# HomeSenseBasic.net
KiCad netlist of a schematic drawn in EAGLE
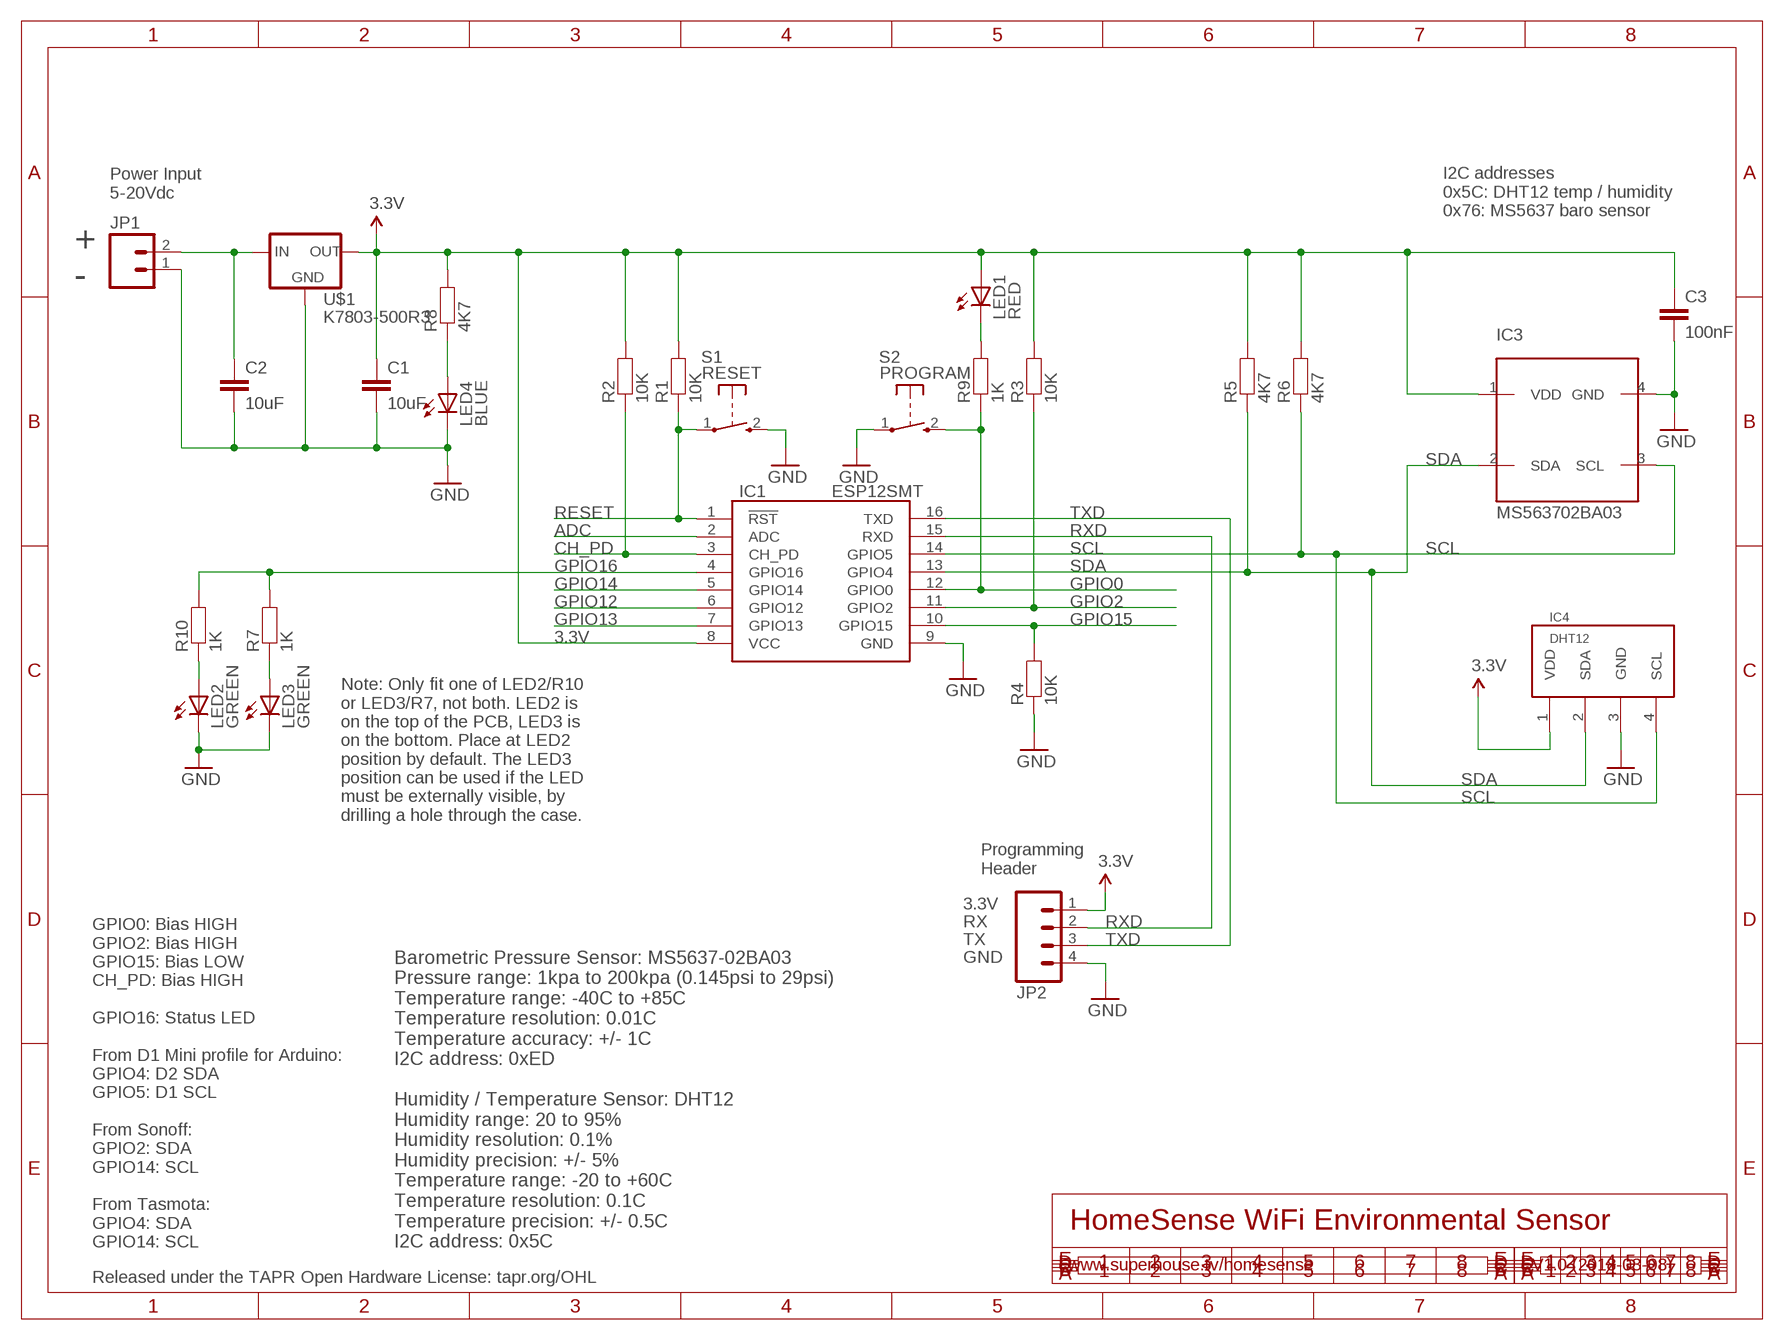
[diagram p0: schematic, sheet 1]

(export (version "E")
  (design (tool "Eeschema 10.0.6"))
  (components
    (comp (ref "C1")
      (value "10uF")
      (footprint "eagle-import:0805")
      (libsource (lib "eagle-import") (part "CAP0805"))
    )
    (comp (ref "C2")
      (value "10uF")
      (footprint "eagle-import:0805")
      (libsource (lib "eagle-import") (part "CAP0805"))
    )
    (comp (ref "C3")
      (value "100nF")
      (footprint "eagle-import:0603")
      (libsource (lib "eagle-import") (part "CAP0603"))
    )
    (comp (ref "IC1")
      (value "ESP12SMT")
      (footprint "eagle-import:ESP12")
      (libsource (lib "eagle-import") (part "ESP12SMT"))
    )
    (comp (ref "IC3")
      (value "MS563702BA03")
      (footprint "eagle-import:MS5637")
      (libsource (lib "eagle-import") (part "MS563702BA03"))
    )
    (comp (ref "IC4")
      (value "DHT12")
      (footprint "eagle-import:DHT12")
      (libsource (lib "eagle-import") (part "DHT12FLAT"))
    )
    (comp (ref "JP1")
      (value "M02PTH")
      (footprint "eagle-import:1X02")
      (libsource (lib "eagle-import") (part "M02PTH"))
    )
    (comp (ref "JP2")
      (value "M04PTH")
      (footprint "eagle-import:1X04")
      (libsource (lib "eagle-import") (part "M04PTH"))
    )
    (comp (ref "LED1")
      (value "RED")
      (footprint "eagle-import:LED-0603")
      (libsource (lib "eagle-import") (part "LED0603"))
    )
    (comp (ref "LED2")
      (value "GREEN")
      (footprint "eagle-import:LED-0603")
      (libsource (lib "eagle-import") (part "LED0603"))
    )
    (comp (ref "LED3")
      (value "GREEN")
      (footprint "eagle-import:LED-0603")
      (libsource (lib "eagle-import") (part "LED0603"))
    )
    (comp (ref "LED4")
      (value "BLUE")
      (footprint "eagle-import:LED-0603")
      (libsource (lib "eagle-import") (part "LED0603"))
    )
    (comp (ref "R1")
      (value "10K")
      (footprint "eagle-import:0603")
      (libsource (lib "eagle-import") (part "RESISTOR0603"))
    )
    (comp (ref "R2")
      (value "10K")
      (footprint "eagle-import:0603")
      (libsource (lib "eagle-import") (part "RESISTOR0603"))
    )
    (comp (ref "R3")
      (value "10K")
      (footprint "eagle-import:0603")
      (libsource (lib "eagle-import") (part "RESISTOR0603"))
    )
    (comp (ref "R4")
      (value "10K")
      (footprint "eagle-import:0603")
      (libsource (lib "eagle-import") (part "RESISTOR0603"))
    )
    (comp (ref "R5")
      (value "4K7")
      (footprint "eagle-import:0603")
      (libsource (lib "eagle-import") (part "RESISTOR0603"))
    )
    (comp (ref "R6")
      (value "4K7")
      (footprint "eagle-import:0603")
      (libsource (lib "eagle-import") (part "RESISTOR0603"))
    )
    (comp (ref "R7")
      (value "1K")
      (footprint "eagle-import:0603")
      (libsource (lib "eagle-import") (part "RESISTOR0603"))
    )
    (comp (ref "R8")
      (value "4K7")
      (footprint "eagle-import:0603")
      (libsource (lib "eagle-import") (part "RESISTOR0603"))
    )
    (comp (ref "R9")
      (value "1K")
      (footprint "eagle-import:0603")
      (libsource (lib "eagle-import") (part "RESISTOR0603"))
    )
    (comp (ref "R10")
      (value "1K")
      (footprint "eagle-import:0603")
      (libsource (lib "eagle-import") (part "RESISTOR0603"))
    )
    (comp (ref "S1")
      (value "RESET")
      (footprint "eagle-import:TACTILE_SWITCH_SMD_2PIN_TINY")
      (libsource (lib "eagle-import") (part "TAC_SWITCH_2PINSMT"))
    )
    (comp (ref "S2")
      (value "PROGRAM")
      (footprint "eagle-import:TACTILE_SWITCH_SMD_2PIN_TINY")
      (libsource (lib "eagle-import") (part "TAC_SWITCH_2PINSMT"))
    )
    (comp (ref "U$1")
      (value "K7803-500R3")
      (footprint "eagle-import:K78XX-500R3")
      (libsource (lib "eagle-import") (part "K78XX-500R3"))
    )
  )
  (nets
    (net (code "1") (name "/ADC") (class "Default")
      (node (ref "IC1") (pin "2") (pinfunction "ADC_2") (pintype "input"))
    )
    (net (code "2") (name "/CH_PD") (class "Default")
      (node (ref "IC1") (pin "3") (pinfunction "CH_PD_3") (pintype "input"))
      (node (ref "R2") (pin "1") (pinfunction "1_1") (pintype "passive"))
    )
    (net (code "3") (name "/GPIO0") (class "Default")
      (node (ref "IC1") (pin "12") (pinfunction "GPIO0_12") (pintype "bidirectional"))
      (node (ref "R9") (pin "1") (pinfunction "1_1") (pintype "passive"))
      (node (ref "S2") (pin "2") (pinfunction "S_2") (pintype "passive"))
    )
    (net (code "4") (name "/GPIO2") (class "Default")
      (node (ref "IC1") (pin "11") (pinfunction "GPIO2_11") (pintype "bidirectional"))
      (node (ref "R3") (pin "1") (pinfunction "1_1") (pintype "passive"))
    )
    (net (code "5") (name "/GPIO12") (class "Default")
      (node (ref "IC1") (pin "6") (pinfunction "GPIO12_6") (pintype "bidirectional"))
    )
    (net (code "6") (name "/GPIO13") (class "Default")
      (node (ref "IC1") (pin "7") (pinfunction "GPIO13_7") (pintype "bidirectional"))
    )
    (net (code "7") (name "/GPIO14") (class "Default")
      (node (ref "IC1") (pin "5") (pinfunction "GPIO14_5") (pintype "bidirectional"))
    )
    (net (code "8") (name "/GPIO15") (class "Default")
      (node (ref "IC1") (pin "10") (pinfunction "GPIO15_10") (pintype "bidirectional"))
      (node (ref "R4") (pin "2") (pinfunction "2_2") (pintype "passive"))
    )
    (net (code "9") (name "/GPIO16") (class "Default")
      (node (ref "IC1") (pin "4") (pinfunction "GPIO16_4") (pintype "bidirectional"))
      (node (ref "R10") (pin "2") (pinfunction "2_2") (pintype "passive"))
      (node (ref "R7") (pin "2") (pinfunction "2_2") (pintype "passive"))
    )
    (net (code "10") (name "/RESET") (class "Default")
      (node (ref "IC1") (pin "1") (pinfunction "~{RST}_1") (pintype "bidirectional"))
      (node (ref "R1") (pin "1") (pinfunction "1_1") (pintype "passive"))
      (node (ref "S1") (pin "1") (pinfunction "P_1") (pintype "passive"))
    )
    (net (code "11") (name "/RXD") (class "Default")
      (node (ref "IC1") (pin "15") (pinfunction "RXD_15") (pintype "input"))
      (node (ref "JP2") (pin "2") (pinfunction "2_2") (pintype "passive"))
    )
    (net (code "12") (name "/SCL") (class "Default")
      (node (ref "IC1") (pin "14") (pinfunction "GPIO5_14") (pintype "bidirectional"))
      (node (ref "IC3") (pin "3") (pinfunction "SCL_3") (pintype "bidirectional"))
      (node (ref "IC4") (pin "4") (pinfunction "SCL_4") (pintype "bidirectional"))
      (node (ref "R6") (pin "1") (pinfunction "1_1") (pintype "passive"))
    )
    (net (code "13") (name "/SDA") (class "Default")
      (node (ref "IC1") (pin "13") (pinfunction "GPIO4_13") (pintype "bidirectional"))
      (node (ref "IC3") (pin "2") (pinfunction "SDA_2") (pintype "bidirectional"))
      (node (ref "IC4") (pin "2") (pinfunction "SDA_2") (pintype "bidirectional"))
      (node (ref "R5") (pin "1") (pinfunction "1_1") (pintype "passive"))
    )
    (net (code "14") (name "/TXD") (class "Default")
      (node (ref "IC1") (pin "16") (pinfunction "TXD_16") (pintype "output"))
      (node (ref "JP2") (pin "3") (pinfunction "3_3") (pintype "passive"))
    )
    (net (code "15") (name "3.3V") (class "Default")
      (node (ref "C1") (pin "1") (pinfunction "1_1") (pintype "passive"))
      (node (ref "C3") (pin "1") (pinfunction "1_1") (pintype "passive"))
      (node (ref "IC1") (pin "8") (pinfunction "VCC_8") (pintype "power_in"))
      (node (ref "IC3") (pin "1") (pinfunction "VDD_1") (pintype "bidirectional"))
      (node (ref "IC4") (pin "1") (pinfunction "VDD_1") (pintype "bidirectional"))
      (node (ref "JP2") (pin "1") (pinfunction "1_1") (pintype "passive"))
      (node (ref "LED1") (pin "A") (pinfunction "A_A") (pintype "passive"))
      (node (ref "R1") (pin "2") (pinfunction "2_2") (pintype "passive"))
      (node (ref "R2") (pin "2") (pinfunction "2_2") (pintype "passive"))
      (node (ref "R3") (pin "2") (pinfunction "2_2") (pintype "passive"))
      (node (ref "R5") (pin "2") (pinfunction "2_2") (pintype "passive"))
      (node (ref "R6") (pin "2") (pinfunction "2_2") (pintype "passive"))
      (node (ref "R8") (pin "2") (pinfunction "2_2") (pintype "passive"))
      (node (ref "U$1") (pin "3") (pinfunction "OUT_3") (pintype "output"))
    )
    (net (code "16") (name "GND") (class "Default")
      (node (ref "C1") (pin "2") (pinfunction "2_2") (pintype "passive"))
      (node (ref "C2") (pin "2") (pinfunction "2_2") (pintype "passive"))
      (node (ref "C3") (pin "2") (pinfunction "2_2") (pintype "passive"))
      (node (ref "IC1") (pin "9") (pinfunction "GND_9") (pintype "power_in"))
      (node (ref "IC3") (pin "4") (pinfunction "GND_4") (pintype "bidirectional"))
      (node (ref "IC4") (pin "3") (pinfunction "GND_3") (pintype "bidirectional"))
      (node (ref "JP1") (pin "1") (pinfunction "1_1") (pintype "passive"))
      (node (ref "JP2") (pin "4") (pinfunction "4_4") (pintype "passive"))
      (node (ref "LED2") (pin "C") (pinfunction "C_C") (pintype "passive"))
      (node (ref "LED3") (pin "C") (pinfunction "C_C") (pintype "passive"))
      (node (ref "LED4") (pin "C") (pinfunction "C_C") (pintype "passive"))
      (node (ref "R4") (pin "1") (pinfunction "1_1") (pintype "passive"))
      (node (ref "S1") (pin "2") (pinfunction "S_2") (pintype "passive"))
      (node (ref "S2") (pin "1") (pinfunction "P_1") (pintype "passive"))
      (node (ref "U$1") (pin "2") (pinfunction "GND_2") (pintype "input"))
    )
    (net (code "17") (name "Net-(LED1-PadC)") (class "Default")
      (node (ref "LED1") (pin "C") (pinfunction "C_C") (pintype "passive"))
      (node (ref "R9") (pin "2") (pinfunction "2_2") (pintype "passive"))
    )
    (net (code "18") (name "Net-(LED2-PadA)") (class "Default")
      (node (ref "LED2") (pin "A") (pinfunction "A_A") (pintype "passive"))
      (node (ref "R10") (pin "1") (pinfunction "1_1") (pintype "passive"))
    )
    (net (code "19") (name "Net-(LED3-PadA)") (class "Default")
      (node (ref "LED3") (pin "A") (pinfunction "A_A") (pintype "passive"))
      (node (ref "R7") (pin "1") (pinfunction "1_1") (pintype "passive"))
    )
    (net (code "20") (name "Net-(LED4-PadA)") (class "Default")
      (node (ref "LED4") (pin "A") (pinfunction "A_A") (pintype "passive"))
      (node (ref "R8") (pin "1") (pinfunction "1_1") (pintype "passive"))
    )
    (net (code "21") (name "Net-(U$1-IN)") (class "Default")
      (node (ref "C2") (pin "1") (pinfunction "1_1") (pintype "passive"))
      (node (ref "JP1") (pin "2") (pinfunction "2_2") (pintype "passive"))
      (node (ref "U$1") (pin "1") (pinfunction "IN_1") (pintype "input"))
    )
  )
)
